# RrIrArray.net
KiCad netlist of a schematic drawn in Altium Designer
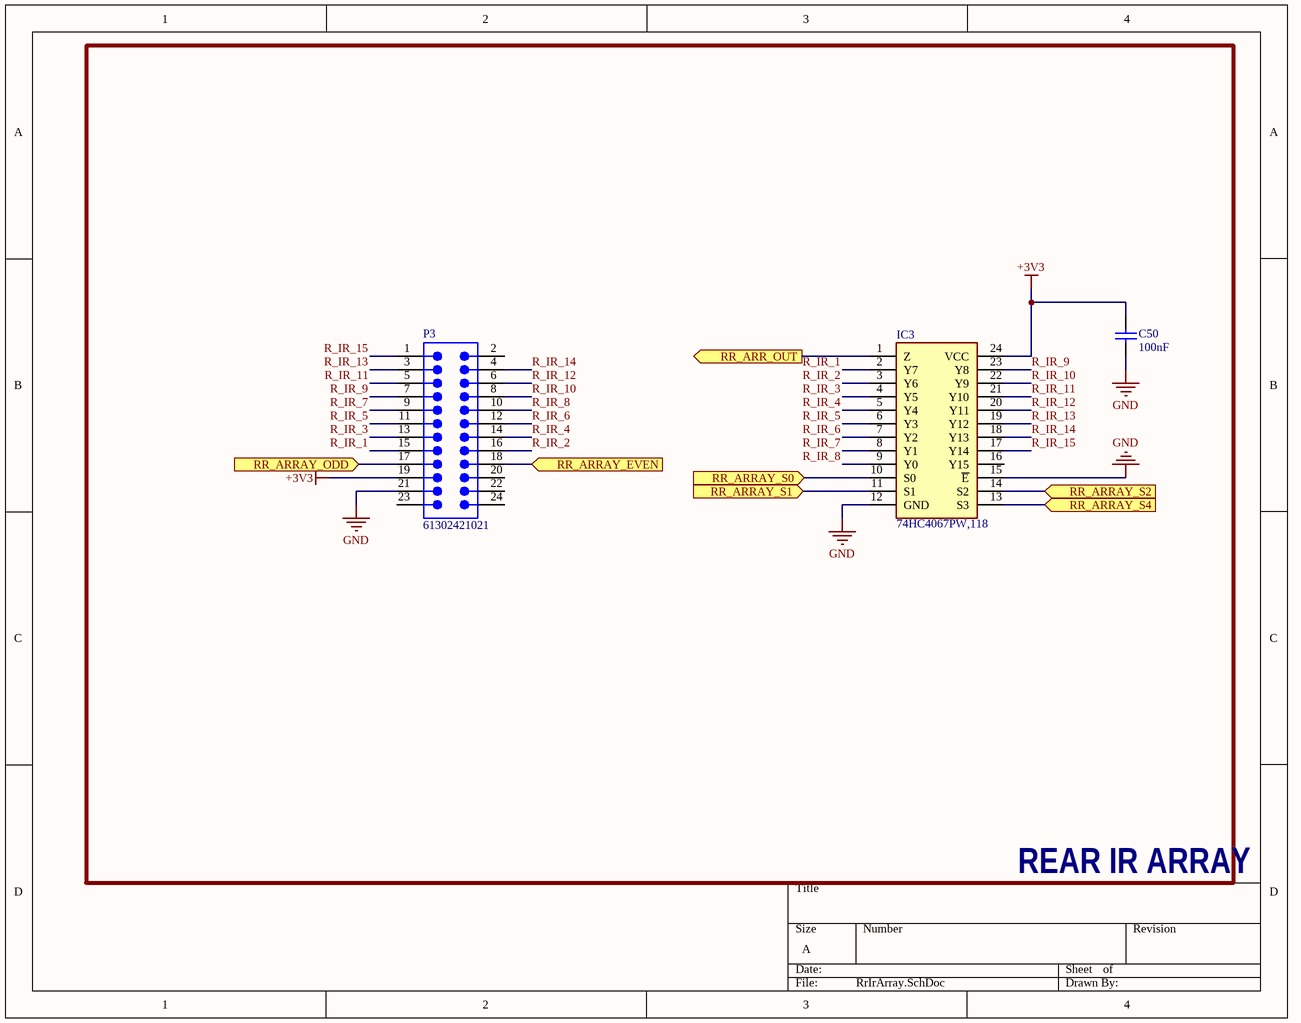
[diagram p0: RrIrArray.SchDoc]

(export (version "E")
  (design (tool "Eeschema 10.0.6"))
  (components
    (comp (ref "C50")
      (value "CL05B104KO5NNNC")
      (footprint "CAPC1050X55X23ML05T13")
      (description "Chip Capacitor, 100 nF, +/- 10%, 16 V, -55 to 125 degC, 0402 (1005 Metric), RoHS, Tape and Reel")
      (fields (field (name "MANUFACTURER") "Samsung Electro-Mechanics") (field (name "CAPACITANCE") "100nF"))
      (libsource (lib "Altium Content Vault") (part "CAP-NP-2"))
    )
    (comp (ref "IC3")
      (value "74HC4067PW,118")
      (footprint "SamacSys:SOP65P640X110-24N")
      (description "Integrated Circuit")
      (fields (field (name "MOUSER PART NUMBER") "771-74HC4067PW-T"))
      (libsource (lib "SamacSys") (part "74HC4067PW,118"))
    )
    (comp (ref "P3")
      (value "61302421021")
      (footprint "61302421021")
      (libsource (lib "Altium Content Vault") (part "Header_Male_2R_24P"))
    )
  )
  (nets
    (net (code "1") (name "+3V3") (class "Default")
      (node (ref "C50") (pin "1") (pinfunction "1_1") (pintype "passive"))
      (node (ref "IC3") (pin "24") (pinfunction "VCC_24") (pintype "passive"))
      (node (ref "P3") (pin "19") (pinfunction "19_19") (pintype "passive"))
    )
    (net (code "2") (name "/RR_ARRAY_EVEN") (class "Default")
      (node (ref "P3") (pin "18") (pinfunction "18_18") (pintype "passive"))
    )
    (net (code "3") (name "/RR_ARRAY_ODD") (class "Default")
      (node (ref "P3") (pin "17") (pinfunction "17_17") (pintype "passive"))
    )
    (net (code "4") (name "/RR_ARRAY_S0") (class "Default")
      (node (ref "IC3") (pin "10") (pinfunction "S0_10") (pintype "passive"))
    )
    (net (code "5") (name "/RR_ARRAY_S1") (class "Default")
      (node (ref "IC3") (pin "11") (pinfunction "S1_11") (pintype "passive"))
    )
    (net (code "6") (name "/RR_ARRAY_S2") (class "Default")
      (node (ref "IC3") (pin "14") (pinfunction "S2_14") (pintype "passive"))
    )
    (net (code "7") (name "/RR_ARRAY_S4") (class "Default")
      (node (ref "IC3") (pin "13") (pinfunction "S3_13") (pintype "passive"))
    )
    (net (code "8") (name "/RR_ARR_OUT") (class "Default")
      (node (ref "IC3") (pin "1") (pinfunction "Z_1") (pintype "passive"))
    )
    (net (code "9") (name "/R_IR_1") (class "Default")
      (node (ref "IC3") (pin "2") (pinfunction "Y7_2") (pintype "passive"))
      (node (ref "P3") (pin "15") (pinfunction "15_15") (pintype "passive"))
    )
    (net (code "10") (name "/R_IR_2") (class "Default")
      (node (ref "IC3") (pin "3") (pinfunction "Y6_3") (pintype "passive"))
      (node (ref "P3") (pin "16") (pinfunction "16_16") (pintype "passive"))
    )
    (net (code "11") (name "/R_IR_3") (class "Default")
      (node (ref "IC3") (pin "4") (pinfunction "Y5_4") (pintype "passive"))
      (node (ref "P3") (pin "13") (pinfunction "13_13") (pintype "passive"))
    )
    (net (code "12") (name "/R_IR_4") (class "Default")
      (node (ref "IC3") (pin "5") (pinfunction "Y4_5") (pintype "passive"))
      (node (ref "P3") (pin "14") (pinfunction "14_14") (pintype "passive"))
    )
    (net (code "13") (name "/R_IR_5") (class "Default")
      (node (ref "IC3") (pin "6") (pinfunction "Y3_6") (pintype "passive"))
      (node (ref "P3") (pin "11") (pinfunction "11_11") (pintype "passive"))
    )
    (net (code "14") (name "/R_IR_6") (class "Default")
      (node (ref "IC3") (pin "7") (pinfunction "Y2_7") (pintype "passive"))
      (node (ref "P3") (pin "12") (pinfunction "12_12") (pintype "passive"))
    )
    (net (code "15") (name "/R_IR_7") (class "Default")
      (node (ref "IC3") (pin "8") (pinfunction "Y1_8") (pintype "passive"))
      (node (ref "P3") (pin "9") (pinfunction "9_9") (pintype "passive"))
    )
    (net (code "16") (name "/R_IR_8") (class "Default")
      (node (ref "IC3") (pin "9") (pinfunction "Y0_9") (pintype "passive"))
      (node (ref "P3") (pin "10") (pinfunction "10_10") (pintype "passive"))
    )
    (net (code "17") (name "/R_IR_9") (class "Default")
      (node (ref "IC3") (pin "23") (pinfunction "Y8_23") (pintype "passive"))
      (node (ref "P3") (pin "7") (pinfunction "7_7") (pintype "passive"))
    )
    (net (code "18") (name "/R_IR_10") (class "Default")
      (node (ref "IC3") (pin "22") (pinfunction "Y9_22") (pintype "passive"))
      (node (ref "P3") (pin "8") (pinfunction "8_8") (pintype "passive"))
    )
    (net (code "19") (name "/R_IR_11") (class "Default")
      (node (ref "IC3") (pin "21") (pinfunction "Y10_21") (pintype "passive"))
      (node (ref "P3") (pin "5") (pinfunction "5_5") (pintype "passive"))
    )
    (net (code "20") (name "/R_IR_12") (class "Default")
      (node (ref "IC3") (pin "20") (pinfunction "Y11_20") (pintype "passive"))
      (node (ref "P3") (pin "6") (pinfunction "6_6") (pintype "passive"))
    )
    (net (code "21") (name "/R_IR_13") (class "Default")
      (node (ref "IC3") (pin "19") (pinfunction "Y12_19") (pintype "passive"))
      (node (ref "P3") (pin "3") (pinfunction "3_3") (pintype "passive"))
    )
    (net (code "22") (name "/R_IR_14") (class "Default")
      (node (ref "IC3") (pin "18") (pinfunction "Y13_18") (pintype "passive"))
      (node (ref "P3") (pin "4") (pinfunction "4_4") (pintype "passive"))
    )
    (net (code "23") (name "/R_IR_15") (class "Default")
      (node (ref "IC3") (pin "17") (pinfunction "Y14_17") (pintype "passive"))
      (node (ref "P3") (pin "1") (pinfunction "1_1") (pintype "passive"))
    )
    (net (code "24") (name "GND") (class "Default")
      (node (ref "C50") (pin "2") (pinfunction "2_2") (pintype "passive"))
      (node (ref "IC3") (pin "12") (pinfunction "GND_12") (pintype "passive"))
      (node (ref "IC3") (pin "15") (pinfunction "~{E}_15") (pintype "passive"))
      (node (ref "P3") (pin "21") (pinfunction "21_21") (pintype "passive"))
    )
    (net (code "25") (name "unconnected-(IC3-Y15-Pad16)") (class "Default")
      (node (ref "IC3") (pin "16") (pinfunction "Y15_16") (pintype "passive"))
    )
    (net (code "26") (name "unconnected-(P3-Pad2)") (class "Default")
      (node (ref "P3") (pin "2") (pinfunction "2_2") (pintype "passive"))
    )
    (net (code "27") (name "unconnected-(P3-Pad20)") (class "Default")
      (node (ref "P3") (pin "20") (pinfunction "20_20") (pintype "passive"))
    )
    (net (code "28") (name "unconnected-(P3-Pad22)") (class "Default")
      (node (ref "P3") (pin "22") (pinfunction "22_22") (pintype "passive"))
    )
    (net (code "29") (name "unconnected-(P3-Pad23)") (class "Default")
      (node (ref "P3") (pin "23") (pinfunction "23_23") (pintype "passive"))
    )
    (net (code "30") (name "unconnected-(P3-Pad24)") (class "Default")
      (node (ref "P3") (pin "24") (pinfunction "24_24") (pintype "passive"))
    )
  )
)
